# Sheet1.net
KiCad netlist of a schematic drawn in Altium Designer
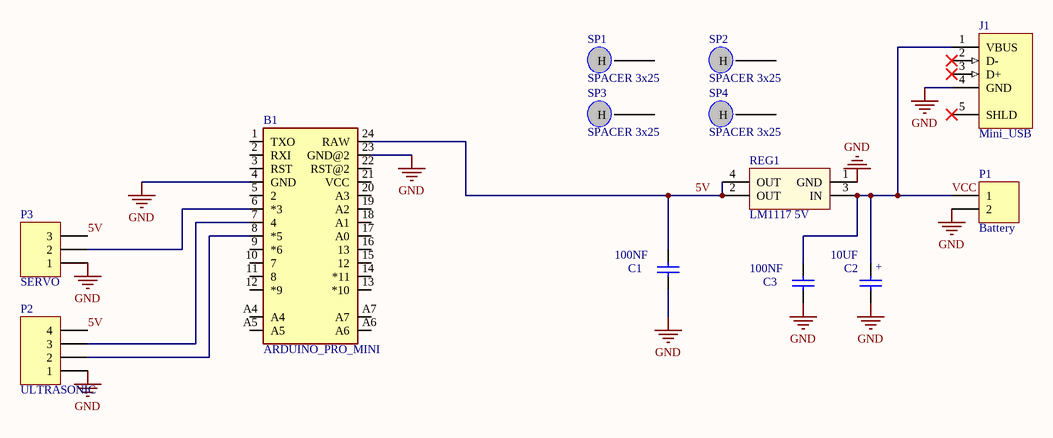
[diagram p0: Sheet1.SchDoc]

(export (version "E")
  (design (tool "Eeschema 10.0.6"))
  (components
    (comp (ref "B1")
      (value "ARDUINO_PRO_MINI")
      (footprint "ARDUINO_PRO_MINI")
      (description "ATmega328 Arduino Pro Mini 328 5V/16MHz AVRÂ® ATmega AVR MCU 8-Bit Embedded Evaluation Board")
      (fields (field (name "MP") "ARDUINO PRO MINI") (field (name "MF") "SparkFun Electronics"))
      (libsource (lib "ARDUINO_PRO_MINI") (part "ARDUINO_PRO_MINI"))
    )
    (comp (ref "C1")
      (value "100NF")
      (footprint "MY_CAP_CERAMIC")
      (description "CAP-100Nf")
      (libsource (lib "AMINLIB") (part "Cap ceramic"))
    )
    (comp (ref "C2")
      (value "10UF")
      (footprint "MY_CAP_POL 4MM")
      (description "CAP-3300Uf")
      (libsource (lib "AMINLIB") (part "Cap Pol_4mm"))
    )
    (comp (ref "C3")
      (value "100NF")
      (footprint "MY_CAP_CERAMIC")
      (description "CAP-100Nf")
      (libsource (lib "AMINLIB") (part "Cap ceramic"))
    )
    (comp (ref "J1")
      (value "Mini_USB")
      (footprint "My_USB")
      (description "USB 2.0, Right Angle, SMT, B Type, Receptacle, 5 Position, Black")
      (fields (field (name "PUBLISHER") "Altium Limited"))
      (libsource (lib "AMINLIB") (part "Mini_USB"))
    )
    (comp (ref "P1")
      (value "Battery")
      (footprint "My_1X02")
      (description "Header, 2-Pin")
      (fields (field (name "PUBLISHER") "Altium Limited"))
      (libsource (lib "AMINLIB") (part "Header 2"))
    )
    (comp (ref "P2")
      (value "ULTRASONIC")
      (footprint "My_1X04")
      (description "Header, 4-Pin")
      (fields (field (name "PUBLISHER") "Altium Limited"))
      (libsource (lib "AMINLIB") (part "Header 4"))
    )
    (comp (ref "P3")
      (value "SERVO")
      (footprint "My_1X03")
      (description "Header, 3-Pin")
      (fields (field (name "PUBLISHER") "Altium Limited"))
      (libsource (lib "AMINLIB") (part "Header 3"))
    )
    (comp (ref "REG1")
      (value "LM1117 5V")
      (footprint "MY_LD1117-3.3")
      (libsource (lib "AMINLIB") (part "LD1117 3.3"))
    )
    (comp (ref "SP1")
      (value "SPACER 3x25")
      (footprint "MY_SPACER 3X25MM")
      (description "SACER 3MM")
      (libsource (lib "AMINLIB") (part "SPACER 3x25"))
    )
    (comp (ref "SP2")
      (value "SPACER 3x25")
      (footprint "MY_SPACER 3X25MM")
      (description "SACER 3MM")
      (libsource (lib "AMINLIB") (part "SPACER 3x25"))
    )
    (comp (ref "SP3")
      (value "SPACER 3x25")
      (footprint "MY_SPACER 3X25MM")
      (description "SACER 3MM")
      (libsource (lib "AMINLIB") (part "SPACER 3x25"))
    )
    (comp (ref "SP4")
      (value "SPACER 3x25")
      (footprint "MY_SPACER 3X25MM")
      (description "SACER 3MM")
      (libsource (lib "AMINLIB") (part "SPACER 3x25"))
    )
  )
  (nets
    (net (code "1") (name "/5V") (class "Default")
      (node (ref "B1") (pin "24") (pinfunction "RAW_24") (pintype "power_in"))
      (node (ref "C1") (pin "2") (pinfunction "2_2") (pintype "passive"))
      (node (ref "P2") (pin "4") (pinfunction "4_4") (pintype "passive"))
      (node (ref "P3") (pin "3") (pinfunction "3_3") (pintype "passive"))
      (node (ref "REG1") (pin "2") (pinfunction "OUT_2") (pintype "power_in"))
      (node (ref "REG1") (pin "4") (pinfunction "OUT_4") (pintype "power_in"))
    )
    (net (code "2") (name "/VCC") (class "Default")
      (node (ref "C2") (pin "+") (pinfunction "+_+") (pintype "passive"))
      (node (ref "C3") (pin "2") (pinfunction "2_2") (pintype "passive"))
      (node (ref "J1") (pin "1") (pinfunction "VBUS_1") (pintype "power_in"))
      (node (ref "P1") (pin "1") (pinfunction "1_1") (pintype "passive"))
      (node (ref "REG1") (pin "3") (pinfunction "IN_3") (pintype "power_in"))
    )
    (net (code "3") (name "GND") (class "Default")
      (node (ref "B1") (pin "23") (pinfunction "GND@2_23") (pintype "power_in"))
      (node (ref "B1") (pin "4") (pinfunction "GND_4") (pintype "power_in"))
      (node (ref "C1") (pin "1") (pinfunction "1_1") (pintype "passive"))
      (node (ref "C2") (pin "-") (pinfunction "-_-") (pintype "passive"))
      (node (ref "C3") (pin "1") (pinfunction "1_1") (pintype "passive"))
      (node (ref "J1") (pin "4") (pinfunction "GND_4") (pintype "power_in"))
      (node (ref "P1") (pin "2") (pinfunction "2_2") (pintype "passive"))
      (node (ref "P2") (pin "1") (pinfunction "1_1") (pintype "passive"))
      (node (ref "P3") (pin "1") (pinfunction "1_1") (pintype "passive"))
      (node (ref "REG1") (pin "1") (pinfunction "GND_1") (pintype "power_in"))
    )
    (net (code "4") (name "Net-(B1-*3)") (class "Default")
      (node (ref "B1") (pin "6") (pinfunction "*3_6") (pintype "bidirectional"))
      (node (ref "P3") (pin "2") (pinfunction "2_2") (pintype "passive"))
    )
    (net (code "5") (name "Net-(B1-*5)") (class "Default")
      (node (ref "B1") (pin "8") (pinfunction "*5_8") (pintype "bidirectional"))
      (node (ref "P2") (pin "2") (pinfunction "2_2") (pintype "passive"))
    )
    (net (code "6") (name "Net-(B1-4)") (class "Default")
      (node (ref "B1") (pin "7") (pinfunction "4_7") (pintype "bidirectional"))
      (node (ref "P2") (pin "3") (pinfunction "3_3") (pintype "passive"))
    )
    (net (code "7") (name "unconnected-(B1-*6-Pad9)") (class "Default")
      (node (ref "B1") (pin "9") (pinfunction "*6_9") (pintype "bidirectional"))
    )
    (net (code "8") (name "unconnected-(B1-*9-Pad12)") (class "Default")
      (node (ref "B1") (pin "12") (pinfunction "*9_12") (pintype "bidirectional"))
    )
    (net (code "9") (name "unconnected-(B1-*10-Pad13)") (class "Default")
      (node (ref "B1") (pin "13") (pinfunction "*10_13") (pintype "bidirectional"))
    )
    (net (code "10") (name "unconnected-(B1-*11-Pad14)") (class "Default")
      (node (ref "B1") (pin "14") (pinfunction "*11_14") (pintype "bidirectional"))
    )
    (net (code "11") (name "unconnected-(B1-2-Pad5)") (class "Default")
      (node (ref "B1") (pin "5") (pinfunction "2_5") (pintype "bidirectional"))
    )
    (net (code "12") (name "unconnected-(B1-7-Pad10)") (class "Default")
      (node (ref "B1") (pin "10") (pinfunction "7_10") (pintype "bidirectional"))
    )
    (net (code "13") (name "unconnected-(B1-8-Pad11)") (class "Default")
      (node (ref "B1") (pin "11") (pinfunction "8_11") (pintype "bidirectional"))
    )
    (net (code "14") (name "unconnected-(B1-12-Pad15)") (class "Default")
      (node (ref "B1") (pin "15") (pinfunction "12_15") (pintype "bidirectional"))
    )
    (net (code "15") (name "unconnected-(B1-13-Pad16)") (class "Default")
      (node (ref "B1") (pin "16") (pinfunction "13_16") (pintype "bidirectional"))
    )
    (net (code "16") (name "unconnected-(B1-A0-Pad17)") (class "Default")
      (node (ref "B1") (pin "17") (pinfunction "A0_17") (pintype "bidirectional"))
    )
    (net (code "17") (name "unconnected-(B1-A1-Pad18)") (class "Default")
      (node (ref "B1") (pin "18") (pinfunction "A1_18") (pintype "bidirectional"))
    )
    (net (code "18") (name "unconnected-(B1-A2-Pad19)") (class "Default")
      (node (ref "B1") (pin "19") (pinfunction "A2_19") (pintype "bidirectional"))
    )
    (net (code "19") (name "unconnected-(B1-A3-Pad20)") (class "Default")
      (node (ref "B1") (pin "20") (pinfunction "A3_20") (pintype "bidirectional"))
    )
    (net (code "20") (name "unconnected-(B1-PadA4)") (class "Default")
      (node (ref "B1") (pin "A4") (pinfunction "A4_A4") (pintype "bidirectional"))
    )
    (net (code "21") (name "unconnected-(B1-PadA5)") (class "Default")
      (node (ref "B1") (pin "A5") (pinfunction "A5_A5") (pintype "bidirectional"))
    )
    (net (code "22") (name "unconnected-(B1-PadA6)") (class "Default")
      (node (ref "B1") (pin "A6") (pinfunction "A6_A6") (pintype "bidirectional"))
    )
    (net (code "23") (name "unconnected-(B1-PadA7)") (class "Default")
      (node (ref "B1") (pin "A7") (pinfunction "A7_A7") (pintype "bidirectional"))
    )
    (net (code "24") (name "unconnected-(B1-RST-Pad3)") (class "Default")
      (node (ref "B1") (pin "3") (pinfunction "RST_3") (pintype "bidirectional"))
    )
    (net (code "25") (name "unconnected-(B1-RST@2-Pad22)") (class "Default")
      (node (ref "B1") (pin "22") (pinfunction "RST@2_22") (pintype "bidirectional"))
    )
    (net (code "26") (name "unconnected-(B1-RXI-Pad2)") (class "Default")
      (node (ref "B1") (pin "2") (pinfunction "RXI_2") (pintype "bidirectional"))
    )
    (net (code "27") (name "unconnected-(B1-TXO-Pad1)") (class "Default")
      (node (ref "B1") (pin "1") (pinfunction "TXO_1") (pintype "bidirectional"))
    )
    (net (code "28") (name "unconnected-(B1-VCC-Pad21)") (class "Default")
      (node (ref "B1") (pin "21") (pinfunction "VCC_21") (pintype "power_in"))
    )
    (net (code "29") (name "unconnected-(J1-D+-Pad3)") (class "Default")
      (node (ref "J1") (pin "3") (pinfunction "D+_3") (pintype "input+no_connect"))
    )
    (net (code "30") (name "unconnected-(J1-D--Pad2)") (class "Default")
      (node (ref "J1") (pin "2") (pinfunction "D-_2") (pintype "input+no_connect"))
    )
    (net (code "31") (name "unconnected-(J1-SHLD-Pad5)") (class "Default")
      (node (ref "J1") (pin "5") (pinfunction "SHLD_5") (pintype "passive+no_connect"))
    )
    (net (code "32") (name "unconnected-(SP1-H-Pad0)") (class "Default")
      (node (ref "SP1") (pin "0") (pinfunction "H_0") (pintype "passive"))
    )
    (net (code "33") (name "unconnected-(SP2-H-Pad0)") (class "Default")
      (node (ref "SP2") (pin "0") (pinfunction "H_0") (pintype "passive"))
    )
    (net (code "34") (name "unconnected-(SP3-H-Pad0)") (class "Default")
      (node (ref "SP3") (pin "0") (pinfunction "H_0") (pintype "passive"))
    )
    (net (code "35") (name "unconnected-(SP4-H-Pad0)") (class "Default")
      (node (ref "SP4") (pin "0") (pinfunction "H_0") (pintype "passive"))
    )
  )
)
